# AD_0_V1_01.net
KiCad netlist of a schematic drawn in Altium Designer
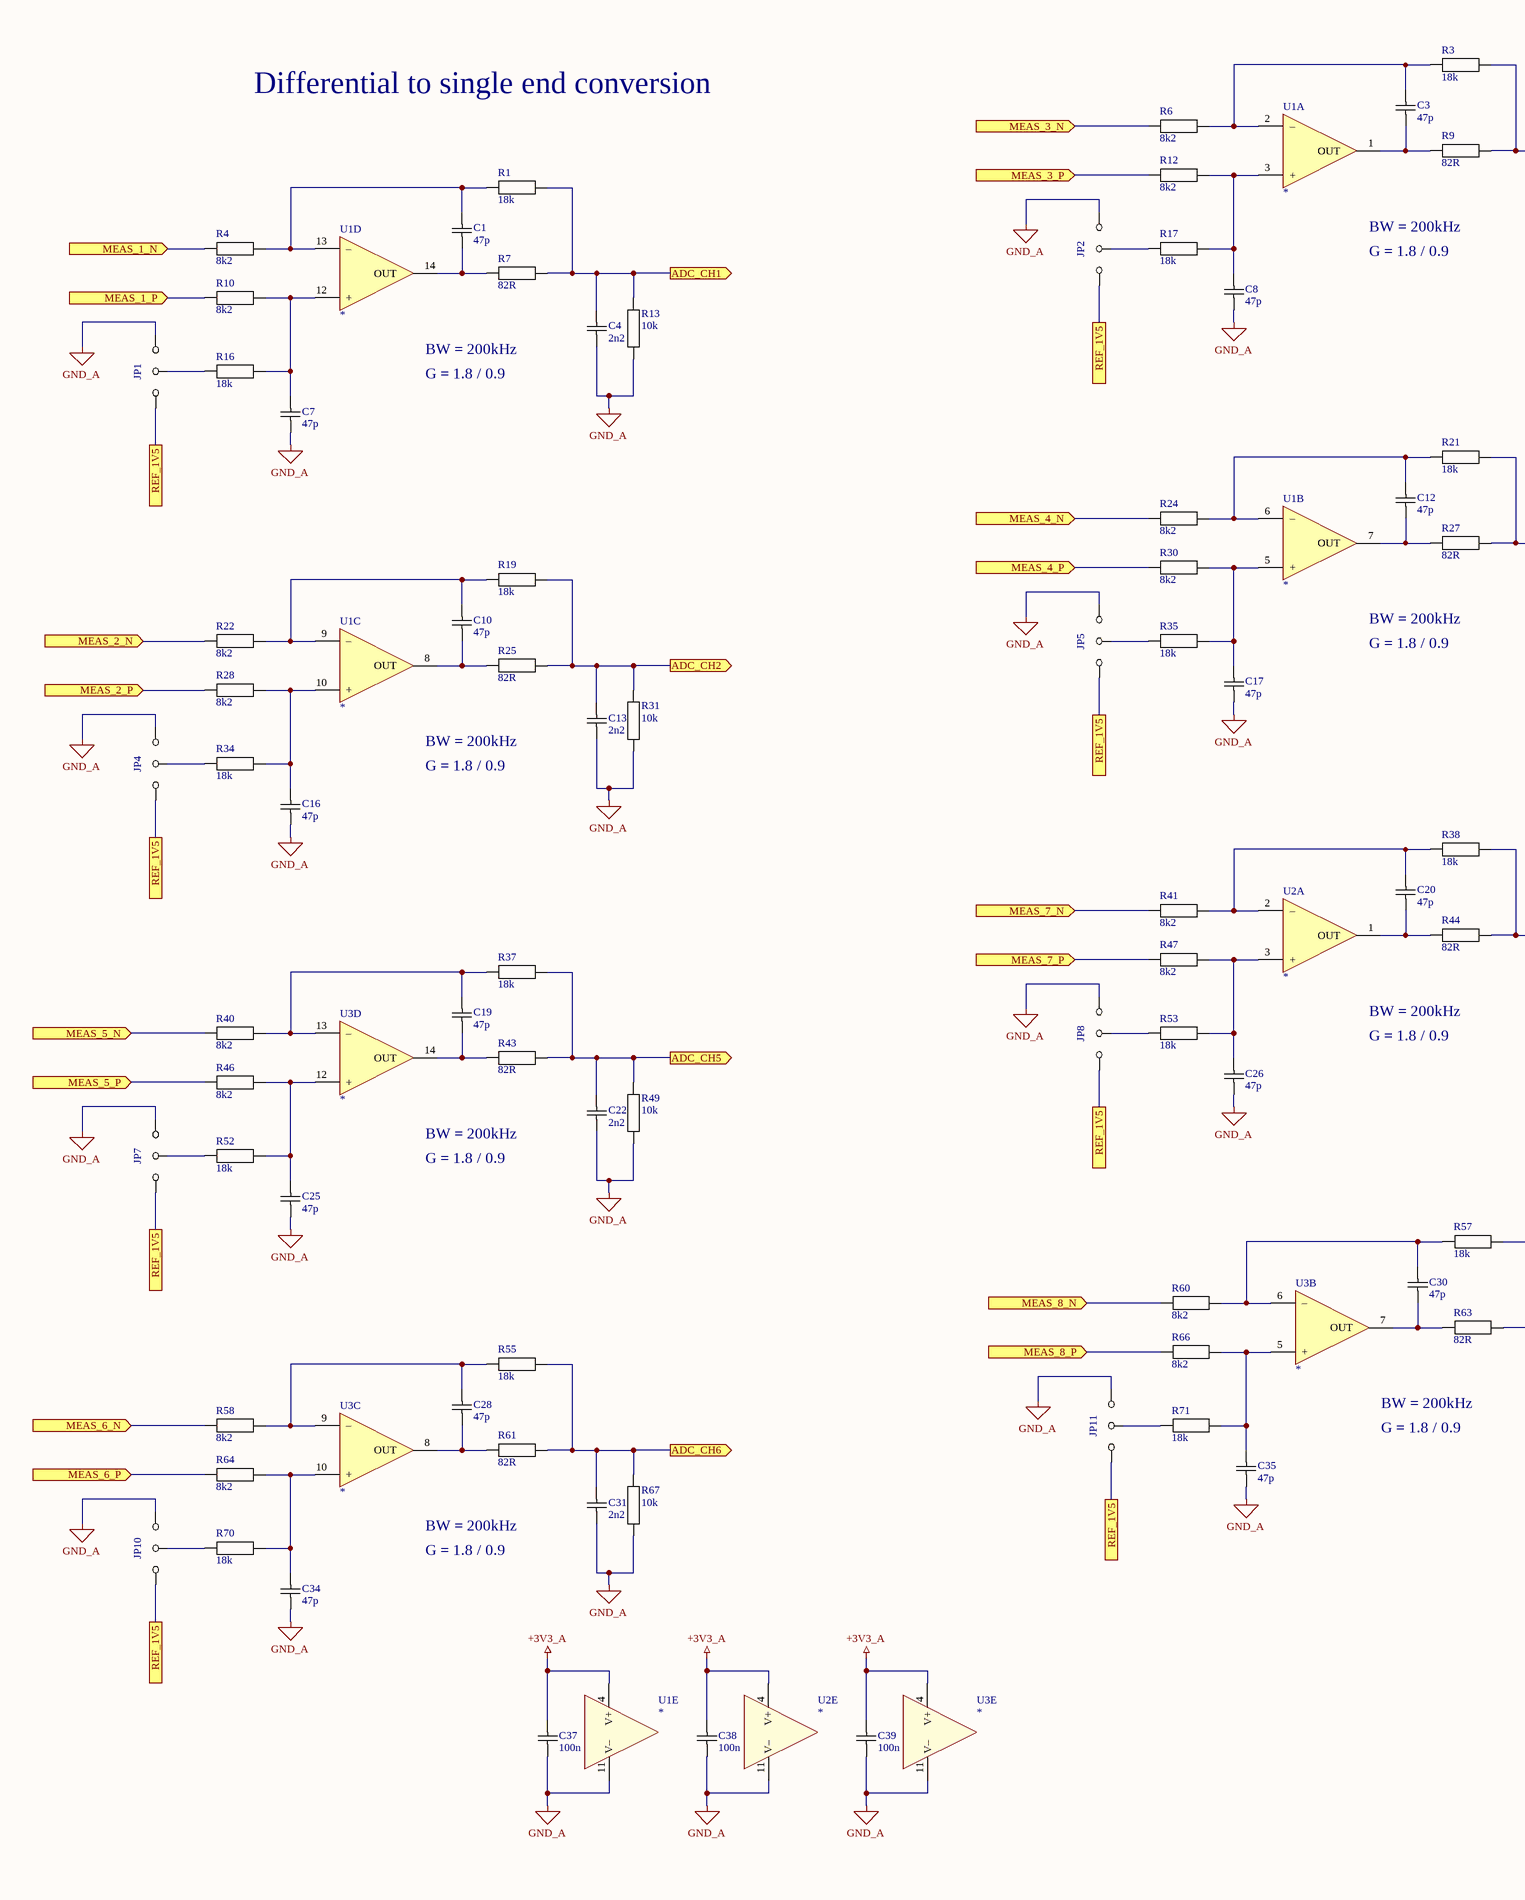
[diagram p0: AD_0_V1_01.SchDoc, left]
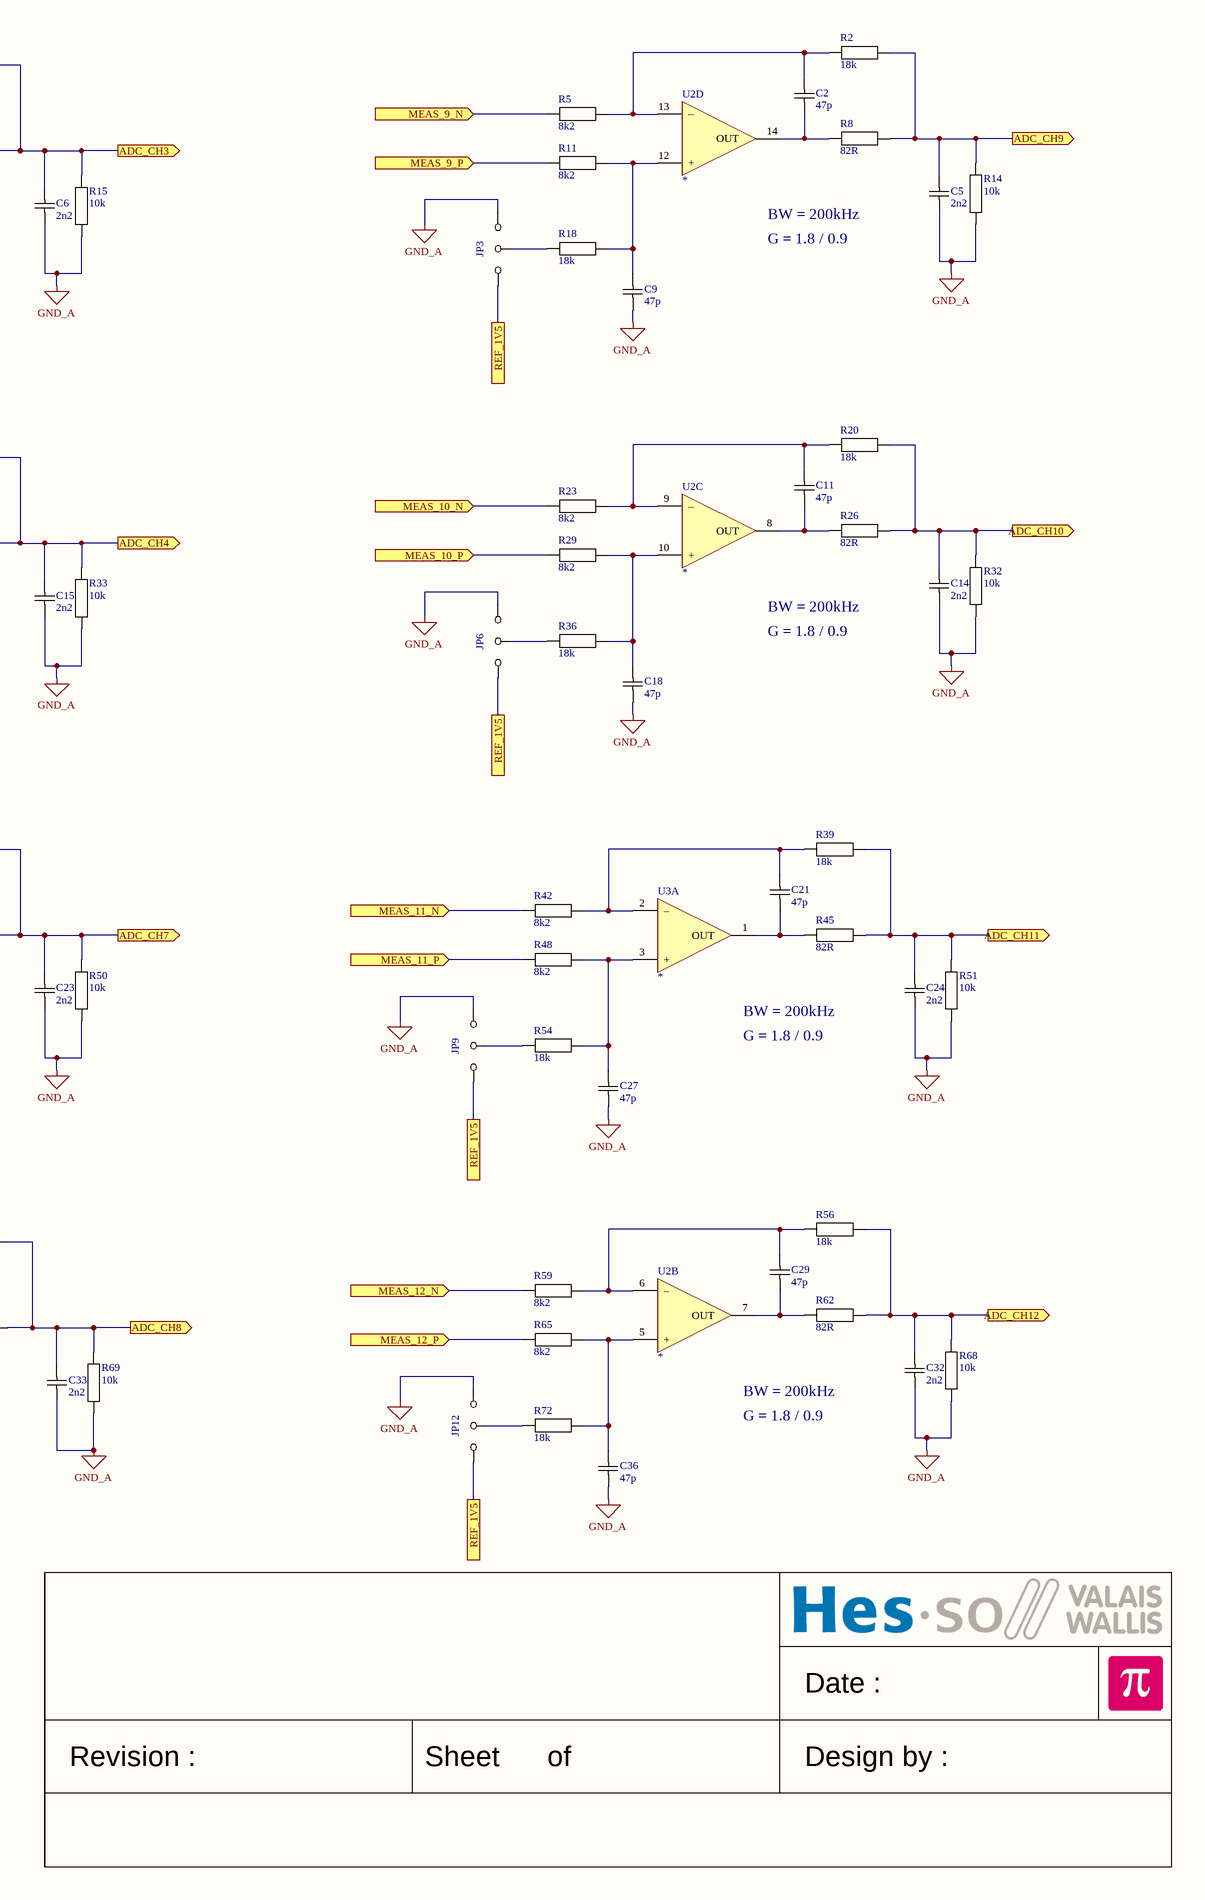
[diagram p1: AD_0_V1_01.SchDoc, right]

(export (version "E")
  (design (tool "Eeschema 10.0.6"))
  (components
    (comp (ref "C1")
      (value "47p")
      (footprint "CAPACITOR 1608 REFLOW")
      (description "Capacitor X7R 10% 50V 1608(0603)")
      (libsource (lib "Capacitor") (part "Capacitor"))
    )
    (comp (ref "C2")
      (value "47p")
      (footprint "CAPACITOR 1608 REFLOW")
      (description "Capacitor X7R 10% 50V 1608(0603)")
      (libsource (lib "Capacitor") (part "Capacitor"))
    )
    (comp (ref "C3")
      (value "47p")
      (footprint "CAPACITOR 1608 REFLOW")
      (description "Capacitor X7R 10% 50V 1608(0603)")
      (libsource (lib "Capacitor") (part "Capacitor"))
    )
    (comp (ref "C4")
      (value "2n2")
      (footprint "CAPACITOR 1608 REFLOW")
      (description "Capacitor X7R 10% 50V 1608(0603)")
      (libsource (lib "Capacitor") (part "Capacitor"))
    )
    (comp (ref "C5")
      (value "2n2")
      (footprint "CAPACITOR 1608 REFLOW")
      (description "Capacitor X7R 10% 50V 1608(0603)")
      (libsource (lib "Capacitor") (part "Capacitor"))
    )
    (comp (ref "C6")
      (value "2n2")
      (footprint "CAPACITOR 1608 REFLOW")
      (description "Capacitor X7R 10% 50V 1608(0603)")
      (libsource (lib "Capacitor") (part "Capacitor"))
    )
    (comp (ref "C7")
      (value "47p")
      (footprint "CAPACITOR 1608 REFLOW")
      (description "Capacitor X7R 10% 50V 1608(0603)")
      (libsource (lib "Capacitor") (part "Capacitor"))
    )
    (comp (ref "C8")
      (value "47p")
      (footprint "CAPACITOR 1608 REFLOW")
      (description "Capacitor X7R 10% 50V 1608(0603)")
      (libsource (lib "Capacitor") (part "Capacitor"))
    )
    (comp (ref "C9")
      (value "47p")
      (footprint "CAPACITOR 1608 REFLOW")
      (description "Capacitor X7R 10% 50V 1608(0603)")
      (libsource (lib "Capacitor") (part "Capacitor"))
    )
    (comp (ref "C10")
      (value "47p")
      (footprint "CAPACITOR 1608 REFLOW")
      (description "Capacitor X7R 10% 50V 1608(0603)")
      (libsource (lib "Capacitor") (part "Capacitor"))
    )
    (comp (ref "C11")
      (value "47p")
      (footprint "CAPACITOR 1608 REFLOW")
      (description "Capacitor X7R 10% 50V 1608(0603)")
      (libsource (lib "Capacitor") (part "Capacitor"))
    )
    (comp (ref "C12")
      (value "47p")
      (footprint "CAPACITOR 1608 REFLOW")
      (description "Capacitor X7R 10% 50V 1608(0603)")
      (libsource (lib "Capacitor") (part "Capacitor"))
    )
    (comp (ref "C13")
      (value "2n2")
      (footprint "CAPACITOR 1608 REFLOW")
      (description "Capacitor X7R 10% 50V 1608(0603)")
      (libsource (lib "Capacitor") (part "Capacitor"))
    )
    (comp (ref "C14")
      (value "2n2")
      (footprint "CAPACITOR 1608 REFLOW")
      (description "Capacitor X7R 10% 50V 1608(0603)")
      (libsource (lib "Capacitor") (part "Capacitor"))
    )
    (comp (ref "C15")
      (value "2n2")
      (footprint "CAPACITOR 1608 REFLOW")
      (description "Capacitor X7R 10% 50V 1608(0603)")
      (libsource (lib "Capacitor") (part "Capacitor"))
    )
    (comp (ref "C16")
      (value "47p")
      (footprint "CAPACITOR 1608 REFLOW")
      (description "Capacitor X7R 10% 50V 1608(0603)")
      (libsource (lib "Capacitor") (part "Capacitor"))
    )
    (comp (ref "C17")
      (value "47p")
      (footprint "CAPACITOR 1608 REFLOW")
      (description "Capacitor X7R 10% 50V 1608(0603)")
      (libsource (lib "Capacitor") (part "Capacitor"))
    )
    (comp (ref "C18")
      (value "47p")
      (footprint "CAPACITOR 1608 REFLOW")
      (description "Capacitor X7R 10% 50V 1608(0603)")
      (libsource (lib "Capacitor") (part "Capacitor"))
    )
    (comp (ref "C19")
      (value "47p")
      (footprint "CAPACITOR 1608 REFLOW")
      (description "Capacitor X7R 10% 50V 1608(0603)")
      (libsource (lib "Capacitor") (part "Capacitor"))
    )
    (comp (ref "C20")
      (value "47p")
      (footprint "CAPACITOR 1608 REFLOW")
      (description "Capacitor X7R 10% 50V 1608(0603)")
      (libsource (lib "Capacitor") (part "Capacitor"))
    )
    (comp (ref "C21")
      (value "47p")
      (footprint "CAPACITOR 1608 REFLOW")
      (description "Capacitor X7R 10% 50V 1608(0603)")
      (libsource (lib "Capacitor") (part "Capacitor"))
    )
    (comp (ref "C22")
      (value "2n2")
      (footprint "CAPACITOR 1608 REFLOW")
      (description "Capacitor X7R 10% 50V 1608(0603)")
      (libsource (lib "Capacitor") (part "Capacitor"))
    )
    (comp (ref "C23")
      (value "2n2")
      (footprint "CAPACITOR 1608 REFLOW")
      (description "Capacitor X7R 10% 50V 1608(0603)")
      (libsource (lib "Capacitor") (part "Capacitor"))
    )
    (comp (ref "C24")
      (value "2n2")
      (footprint "CAPACITOR 1608 REFLOW")
      (description "Capacitor X7R 10% 50V 1608(0603)")
      (libsource (lib "Capacitor") (part "Capacitor"))
    )
    (comp (ref "C25")
      (value "47p")
      (footprint "CAPACITOR 1608 REFLOW")
      (description "Capacitor X7R 10% 50V 1608(0603)")
      (libsource (lib "Capacitor") (part "Capacitor"))
    )
    (comp (ref "C26")
      (value "47p")
      (footprint "CAPACITOR 1608 REFLOW")
      (description "Capacitor X7R 10% 50V 1608(0603)")
      (libsource (lib "Capacitor") (part "Capacitor"))
    )
    (comp (ref "C27")
      (value "47p")
      (footprint "CAPACITOR 1608 REFLOW")
      (description "Capacitor X7R 10% 50V 1608(0603)")
      (libsource (lib "Capacitor") (part "Capacitor"))
    )
    (comp (ref "C28")
      (value "47p")
      (footprint "CAPACITOR 1608 REFLOW")
      (description "Capacitor X7R 10% 50V 1608(0603)")
      (libsource (lib "Capacitor") (part "Capacitor"))
    )
    (comp (ref "C29")
      (value "47p")
      (footprint "CAPACITOR 1608 REFLOW")
      (description "Capacitor X7R 10% 50V 1608(0603)")
      (libsource (lib "Capacitor") (part "Capacitor"))
    )
    (comp (ref "C30")
      (value "47p")
      (footprint "CAPACITOR 1608 REFLOW")
      (description "Capacitor X7R 10% 50V 1608(0603)")
      (libsource (lib "Capacitor") (part "Capacitor"))
    )
    (comp (ref "C31")
      (value "2n2")
      (footprint "CAPACITOR 1608 REFLOW")
      (description "Capacitor X7R 10% 50V 1608(0603)")
      (libsource (lib "Capacitor") (part "Capacitor"))
    )
    (comp (ref "C32")
      (value "2n2")
      (footprint "CAPACITOR 1608 REFLOW")
      (description "Capacitor X7R 10% 50V 1608(0603)")
      (libsource (lib "Capacitor") (part "Capacitor"))
    )
    (comp (ref "C33")
      (value "2n2")
      (footprint "CAPACITOR 1608 REFLOW")
      (description "Capacitor X7R 10% 50V 1608(0603)")
      (libsource (lib "Capacitor") (part "Capacitor"))
    )
    (comp (ref "C34")
      (value "47p")
      (footprint "CAPACITOR 1608 REFLOW")
      (description "Capacitor X7R 10% 50V 1608(0603)")
      (libsource (lib "Capacitor") (part "Capacitor"))
    )
    (comp (ref "C35")
      (value "47p")
      (footprint "CAPACITOR 1608 REFLOW")
      (description "Capacitor X7R 10% 50V 1608(0603)")
      (libsource (lib "Capacitor") (part "Capacitor"))
    )
    (comp (ref "C36")
      (value "47p")
      (footprint "CAPACITOR 1608 REFLOW")
      (description "Capacitor X7R 10% 50V 1608(0603)")
      (libsource (lib "Capacitor") (part "Capacitor"))
    )
    (comp (ref "C37")
      (value "100n")
      (footprint "CAPACITOR 1608 REFLOW")
      (description "Capacitor X7R 10% 50V 1608(0603)")
      (libsource (lib "Capacitor") (part "Capacitor"))
    )
    (comp (ref "C38")
      (value "100n")
      (footprint "CAPACITOR 1608 REFLOW")
      (description "Capacitor X7R 10% 50V 1608(0603)")
      (libsource (lib "Capacitor") (part "Capacitor"))
    )
    (comp (ref "C39")
      (value "100n")
      (footprint "CAPACITOR 1608 REFLOW")
      (description "Capacitor X7R 10% 50V 1608(0603)")
      (libsource (lib "Capacitor") (part "Capacitor"))
    )
    (comp (ref "JP1")
      (value "{Value}")
      (footprint "JUMPER3 SMD 1608")
      (description "JUMPER 3 POS")
      (libsource (lib "Jumper") (part "JUMPER 3 POS"))
    )
    (comp (ref "JP2")
      (value "{Value}")
      (footprint "JUMPER3 SMD 1608")
      (description "JUMPER 3 POS")
      (libsource (lib "Jumper") (part "JUMPER 3 POS"))
    )
    (comp (ref "JP3")
      (value "{Value}")
      (footprint "JUMPER3 SMD 1608")
      (description "JUMPER 3 POS")
      (libsource (lib "Jumper") (part "JUMPER 3 POS"))
    )
    (comp (ref "JP4")
      (value "{Value}")
      (footprint "JUMPER3 SMD 1608")
      (description "JUMPER 3 POS")
      (libsource (lib "Jumper") (part "JUMPER 3 POS"))
    )
    (comp (ref "JP5")
      (value "{Value}")
      (footprint "JUMPER3 SMD 1608")
      (description "JUMPER 3 POS")
      (libsource (lib "Jumper") (part "JUMPER 3 POS"))
    )
    (comp (ref "JP6")
      (value "{Value}")
      (footprint "JUMPER3 SMD 1608")
      (description "JUMPER 3 POS")
      (libsource (lib "Jumper") (part "JUMPER 3 POS"))
    )
    (comp (ref "JP7")
      (value "{Value}")
      (footprint "JUMPER3 SMD 1608")
      (description "JUMPER 3 POS")
      (libsource (lib "Jumper") (part "JUMPER 3 POS"))
    )
    (comp (ref "JP8")
      (value "{Value}")
      (footprint "JUMPER3 SMD 1608")
      (description "JUMPER 3 POS")
      (libsource (lib "Jumper") (part "JUMPER 3 POS"))
    )
    (comp (ref "JP9")
      (value "{Value}")
      (footprint "JUMPER3 SMD 1608")
      (description "JUMPER 3 POS")
      (libsource (lib "Jumper") (part "JUMPER 3 POS"))
    )
    (comp (ref "JP10")
      (value "{Value}")
      (footprint "JUMPER3 SMD 1608")
      (description "JUMPER 3 POS")
      (libsource (lib "Jumper") (part "JUMPER 3 POS"))
    )
    (comp (ref "JP11")
      (value "{Value}")
      (footprint "JUMPER3 SMD 1608")
      (description "JUMPER 3 POS")
      (libsource (lib "Jumper") (part "JUMPER 3 POS"))
    )
    (comp (ref "JP12")
      (value "{Value}")
      (footprint "JUMPER3 SMD 1608")
      (description "JUMPER 3 POS")
      (libsource (lib "Jumper") (part "JUMPER 3 POS"))
    )
    (comp (ref "R1")
      (value "18k")
      (footprint "RESISTOR 1608 REFLOW")
      (description "Resistor 1% 50V 100mW 1608(0603)")
      (libsource (lib "Resistor") (part "Resistor"))
    )
    (comp (ref "R2")
      (value "18k")
      (footprint "RESISTOR 1608 REFLOW")
      (description "Resistor 1% 50V 100mW 1608(0603)")
      (libsource (lib "Resistor") (part "Resistor"))
    )
    (comp (ref "R3")
      (value "18k")
      (footprint "RESISTOR 1608 REFLOW")
      (description "Resistor 1% 50V 100mW 1608(0603)")
      (libsource (lib "Resistor") (part "Resistor"))
    )
    (comp (ref "R4")
      (value "8k2")
      (footprint "RESISTOR 1608 REFLOW")
      (description "Resistor 1% 50V 100mW 1608(0603)")
      (libsource (lib "Resistor") (part "Resistor"))
    )
    (comp (ref "R5")
      (value "8k2")
      (footprint "RESISTOR 1608 REFLOW")
      (description "Resistor 1% 50V 100mW 1608(0603)")
      (libsource (lib "Resistor") (part "Resistor"))
    )
    (comp (ref "R6")
      (value "8k2")
      (footprint "RESISTOR 1608 REFLOW")
      (description "Resistor 1% 50V 100mW 1608(0603)")
      (libsource (lib "Resistor") (part "Resistor"))
    )
    (comp (ref "R7")
      (value "82R")
      (footprint "RESISTOR 1608 REFLOW")
      (description "Resistor 1% 50V 100mW 1608(0603)")
      (libsource (lib "Resistor") (part "Resistor"))
    )
    (comp (ref "R8")
      (value "82R")
      (footprint "RESISTOR 1608 REFLOW")
      (description "Resistor 1% 50V 100mW 1608(0603)")
      (libsource (lib "Resistor") (part "Resistor"))
    )
    (comp (ref "R9")
      (value "82R")
      (footprint "RESISTOR 1608 REFLOW")
      (description "Resistor 1% 50V 100mW 1608(0603)")
      (libsource (lib "Resistor") (part "Resistor"))
    )
    (comp (ref "R10")
      (value "8k2")
      (footprint "RESISTOR 1608 REFLOW")
      (description "Resistor 1% 50V 100mW 1608(0603)")
      (libsource (lib "Resistor") (part "Resistor"))
    )
    (comp (ref "R11")
      (value "8k2")
      (footprint "RESISTOR 1608 REFLOW")
      (description "Resistor 1% 50V 100mW 1608(0603)")
      (libsource (lib "Resistor") (part "Resistor"))
    )
    (comp (ref "R12")
      (value "8k2")
      (footprint "RESISTOR 1608 REFLOW")
      (description "Resistor 1% 50V 100mW 1608(0603)")
      (libsource (lib "Resistor") (part "Resistor"))
    )
    (comp (ref "R13")
      (value "10k")
      (footprint "RESISTOR 1608 REFLOW")
      (description "Resistor 1% 50V 100mW 1608(0603)")
      (libsource (lib "Resistor") (part "Resistor"))
    )
    (comp (ref "R14")
      (value "10k")
      (footprint "RESISTOR 1608 REFLOW")
      (description "Resistor 1% 50V 100mW 1608(0603)")
      (libsource (lib "Resistor") (part "Resistor"))
    )
    (comp (ref "R15")
      (value "10k")
      (footprint "RESISTOR 1608 REFLOW")
      (description "Resistor 1% 50V 100mW 1608(0603)")
      (libsource (lib "Resistor") (part "Resistor"))
    )
    (comp (ref "R16")
      (value "18k")
      (footprint "RESISTOR 1608 REFLOW")
      (description "Resistor 1% 50V 100mW 1608(0603)")
      (libsource (lib "Resistor") (part "Resistor"))
    )
    (comp (ref "R17")
      (value "18k")
      (footprint "RESISTOR 1608 REFLOW")
      (description "Resistor 1% 50V 100mW 1608(0603)")
      (libsource (lib "Resistor") (part "Resistor"))
    )
    (comp (ref "R18")
      (value "18k")
      (footprint "RESISTOR 1608 REFLOW")
      (description "Resistor 1% 50V 100mW 1608(0603)")
      (libsource (lib "Resistor") (part "Resistor"))
    )
    (comp (ref "R19")
      (value "18k")
      (footprint "RESISTOR 1608 REFLOW")
      (description "Resistor 1% 50V 100mW 1608(0603)")
      (libsource (lib "Resistor") (part "Resistor"))
    )
    (comp (ref "R20")
      (value "18k")
      (footprint "RESISTOR 1608 REFLOW")
      (description "Resistor 1% 50V 100mW 1608(0603)")
      (libsource (lib "Resistor") (part "Resistor"))
    )
    (comp (ref "R21")
      (value "18k")
      (footprint "RESISTOR 1608 REFLOW")
      (description "Resistor 1% 50V 100mW 1608(0603)")
      (libsource (lib "Resistor") (part "Resistor"))
    )
    (comp (ref "R22")
      (value "8k2")
      (footprint "RESISTOR 1608 REFLOW")
      (description "Resistor 1% 50V 100mW 1608(0603)")
      (libsource (lib "Resistor") (part "Resistor"))
    )
    (comp (ref "R23")
      (value "8k2")
      (footprint "RESISTOR 1608 REFLOW")
      (description "Resistor 1% 50V 100mW 1608(0603)")
      (libsource (lib "Resistor") (part "Resistor"))
    )
    (comp (ref "R24")
      (value "8k2")
      (footprint "RESISTOR 1608 REFLOW")
      (description "Resistor 1% 50V 100mW 1608(0603)")
      (libsource (lib "Resistor") (part "Resistor"))
    )
    (comp (ref "R25")
      (value "82R")
      (footprint "RESISTOR 1608 REFLOW")
      (description "Resistor 1% 50V 100mW 1608(0603)")
      (libsource (lib "Resistor") (part "Resistor"))
    )
    (comp (ref "R26")
      (value "82R")
      (footprint "RESISTOR 1608 REFLOW")
      (description "Resistor 1% 50V 100mW 1608(0603)")
      (libsource (lib "Resistor") (part "Resistor"))
    )
    (comp (ref "R27")
      (value "82R")
      (footprint "RESISTOR 1608 REFLOW")
      (description "Resistor 1% 50V 100mW 1608(0603)")
      (libsource (lib "Resistor") (part "Resistor"))
    )
    (comp (ref "R28")
      (value "8k2")
      (footprint "RESISTOR 1608 REFLOW")
      (description "Resistor 1% 50V 100mW 1608(0603)")
      (libsource (lib "Resistor") (part "Resistor"))
    )
    (comp (ref "R29")
      (value "8k2")
      (footprint "RESISTOR 1608 REFLOW")
      (description "Resistor 1% 50V 100mW 1608(0603)")
      (libsource (lib "Resistor") (part "Resistor"))
    )
    (comp (ref "R30")
      (value "8k2")
      (footprint "RESISTOR 1608 REFLOW")
      (description "Resistor 1% 50V 100mW 1608(0603)")
      (libsource (lib "Resistor") (part "Resistor"))
    )
    (comp (ref "R31")
      (value "10k")
      (footprint "RESISTOR 1608 REFLOW")
      (description "Resistor 1% 50V 100mW 1608(0603)")
      (libsource (lib "Resistor") (part "Resistor"))
    )
    (comp (ref "R32")
      (value "10k")
      (footprint "RESISTOR 1608 REFLOW")
      (description "Resistor 1% 50V 100mW 1608(0603)")
      (libsource (lib "Resistor") (part "Resistor"))
    )
    (comp (ref "R33")
      (value "10k")
      (footprint "RESISTOR 1608 REFLOW")
      (description "Resistor 1% 50V 100mW 1608(0603)")
      (libsource (lib "Resistor") (part "Resistor"))
    )
    (comp (ref "R34")
      (value "18k")
      (footprint "RESISTOR 1608 REFLOW")
      (description "Resistor 1% 50V 100mW 1608(0603)")
      (libsource (lib "Resistor") (part "Resistor"))
    )
    (comp (ref "R35")
      (value "18k")
      (footprint "RESISTOR 1608 REFLOW")
      (description "Resistor 1% 50V 100mW 1608(0603)")
      (libsource (lib "Resistor") (part "Resistor"))
    )
    (comp (ref "R36")
      (value "18k")
      (footprint "RESISTOR 1608 REFLOW")
      (description "Resistor 1% 50V 100mW 1608(0603)")
      (libsource (lib "Resistor") (part "Resistor"))
    )
    (comp (ref "R37")
      (value "18k")
      (footprint "RESISTOR 1608 REFLOW")
      (description "Resistor 1% 50V 100mW 1608(0603)")
      (libsource (lib "Resistor") (part "Resistor"))
    )
    (comp (ref "R38")
      (value "18k")
      (footprint "RESISTOR 1608 REFLOW")
      (description "Resistor 1% 50V 100mW 1608(0603)")
      (libsource (lib "Resistor") (part "Resistor"))
    )
    (comp (ref "R39")
      (value "18k")
      (footprint "RESISTOR 1608 REFLOW")
      (description "Resistor 1% 50V 100mW 1608(0603)")
      (libsource (lib "Resistor") (part "Resistor"))
    )
    (comp (ref "R40")
      (value "8k2")
      (footprint "RESISTOR 1608 REFLOW")
      (description "Resistor 1% 50V 100mW 1608(0603)")
      (libsource (lib "Resistor") (part "Resistor"))
    )
    (comp (ref "R41")
      (value "8k2")
      (footprint "RESISTOR 1608 REFLOW")
      (description "Resistor 1% 50V 100mW 1608(0603)")
      (libsource (lib "Resistor") (part "Resistor"))
    )
    (comp (ref "R42")
      (value "8k2")
      (footprint "RESISTOR 1608 REFLOW")
      (description "Resistor 1% 50V 100mW 1608(0603)")
      (libsource (lib "Resistor") (part "Resistor"))
    )
    (comp (ref "R43")
      (value "82R")
      (footprint "RESISTOR 1608 REFLOW")
      (description "Resistor 1% 50V 100mW 1608(0603)")
      (libsource (lib "Resistor") (part "Resistor"))
    )
    (comp (ref "R44")
      (value "82R")
      (footprint "RESISTOR 1608 REFLOW")
      (description "Resistor 1% 50V 100mW 1608(0603)")
      (libsource (lib "Resistor") (part "Resistor"))
    )
    (comp (ref "R45")
      (value "82R")
      (footprint "RESISTOR 1608 REFLOW")
      (description "Resistor 1% 50V 100mW 1608(0603)")
      (libsource (lib "Resistor") (part "Resistor"))
    )
    (comp (ref "R46")
      (value "8k2")
      (footprint "RESISTOR 1608 REFLOW")
      (description "Resistor 1% 50V 100mW 1608(0603)")
      (libsource (lib "Resistor") (part "Resistor"))
    )
    (comp (ref "R47")
      (value "8k2")
      (footprint "RESISTOR 1608 REFLOW")
      (description "Resistor 1% 50V 100mW 1608(0603)")
      (libsource (lib "Resistor") (part "Resistor"))
    )
    (comp (ref "R48")
      (value "8k2")
      (footprint "RESISTOR 1608 REFLOW")
      (description "Resistor 1% 50V 100mW 1608(0603)")
      (libsource (lib "Resistor") (part "Resistor"))
    )
    (comp (ref "R49")
      (value "10k")
      (footprint "RESISTOR 1608 REFLOW")
      (description "Resistor 1% 50V 100mW 1608(0603)")
      (libsource (lib "Resistor") (part "Resistor"))
    )
    (comp (ref "R50")
      (value "10k")
      (footprint "RESISTOR 1608 REFLOW")
      (description "Resistor 1% 50V 100mW 1608(0603)")
      (libsource (lib "Resistor") (part "Resistor"))
    )
    (comp (ref "R51")
      (value "10k")
      (footprint "RESISTOR 1608 REFLOW")
      (description "Resistor 1% 50V 100mW 1608(0603)")
      (libsource (lib "Resistor") (part "Resistor"))
    )
    (comp (ref "R52")
      (value "18k")
      (footprint "RESISTOR 1608 REFLOW")
      (description "Resistor 1% 50V 100mW 1608(0603)")
      (libsource (lib "Resistor") (part "Resistor"))
    )
    (comp (ref "R53")
      (value "18k")
      (footprint "RESISTOR 1608 REFLOW")
      (description "Resistor 1% 50V 100mW 1608(0603)")
      (libsource (lib "Resistor") (part "Resistor"))
    )
    (comp (ref "R54")
      (value "18k")
      (footprint "RESISTOR 1608 REFLOW")
      (description "Resistor 1% 50V 100mW 1608(0603)")
      (libsource (lib "Resistor") (part "Resistor"))
    )
    (comp (ref "R55")
      (value "18k")
      (footprint "RESISTOR 1608 REFLOW")
      (description "Resistor 1% 50V 100mW 1608(0603)")
      (libsource (lib "Resistor") (part "Resistor"))
    )
    (comp (ref "R56")
      (value "18k")
      (footprint "RESISTOR 1608 REFLOW")
      (description "Resistor 1% 50V 100mW 1608(0603)")
      (libsource (lib "Resistor") (part "Resistor"))
    )
    (comp (ref "R57")
      (value "18k")
      (footprint "RESISTOR 1608 REFLOW")
      (description "Resistor 1% 50V 100mW 1608(0603)")
      (libsource (lib "Resistor") (part "Resistor"))
    )
    (comp (ref "R58")
      (value "8k2")
      (footprint "RESISTOR 1608 REFLOW")
      (description "Resistor 1% 50V 100mW 1608(0603)")
      (libsource (lib "Resistor") (part "Resistor"))
    )
    (comp (ref "R59")
      (value "8k2")
      (footprint "RESISTOR 1608 REFLOW")
      (description "Resistor 1% 50V 100mW 1608(0603)")
      (libsource (lib "Resistor") (part "Resistor"))
    )
    (comp (ref "R60")
      (value "8k2")
      (footprint "RESISTOR 1608 REFLOW")
      (description "Resistor 1% 50V 100mW 1608(0603)")
      (libsource (lib "Resistor") (part "Resistor"))
    )
    (comp (ref "R61")
      (value "82R")
      (footprint "RESISTOR 1608 REFLOW")
      (description "Resistor 1% 50V 100mW 1608(0603)")
      (libsource (lib "Resistor") (part "Resistor"))
    )
    (comp (ref "R62")
      (value "82R")
      (footprint "RESISTOR 1608 REFLOW")
      (description "Resistor 1% 50V 100mW 1608(0603)")
      (libsource (lib "Resistor") (part "Resistor"))
    )
    (comp (ref "R63")
      (value "82R")
      (footprint "RESISTOR 1608 REFLOW")
      (description "Resistor 1% 50V 100mW 1608(0603)")
      (libsource (lib "Resistor") (part "Resistor"))
    )
    (comp (ref "R64")
      (value "8k2")
      (footprint "RESISTOR 1608 REFLOW")
      (description "Resistor 1% 50V 100mW 1608(0603)")
      (libsource (lib "Resistor") (part "Resistor"))
    )
    (comp (ref "R65")
      (value "8k2")
      (footprint "RESISTOR 1608 REFLOW")
      (description "Resistor 1% 50V 100mW 1608(0603)")
      (libsource (lib "Resistor") (part "Resistor"))
    )
    (comp (ref "R66")
      (value "8k2")
      (footprint "RESISTOR 1608 REFLOW")
      (description "Resistor 1% 50V 100mW 1608(0603)")
      (libsource (lib "Resistor") (part "Resistor"))
    )
    (comp (ref "R67")
      (value "10k")
      (footprint "RESISTOR 1608 REFLOW")
      (description "Resistor 1% 50V 100mW 1608(0603)")
      (libsource (lib "Resistor") (part "Resistor"))
    )
    (comp (ref "R68")
      (value "10k")
      (footprint "RESISTOR 1608 REFLOW")
      (description "Resistor 1% 50V 100mW 1608(0603)")
      (libsource (lib "Resistor") (part "Resistor"))
    )
    (comp (ref "R69")
      (value "10k")
      (footprint "RESISTOR 1608 REFLOW")
      (description "Resistor 1% 50V 100mW 1608(0603)")
      (libsource (lib "Resistor") (part "Resistor"))
    )
    (comp (ref "R70")
      (value "18k")
      (footprint "RESISTOR 1608 REFLOW")
      (description "Resistor 1% 50V 100mW 1608(0603)")
      (libsource (lib "Resistor") (part "Resistor"))
    )
    (comp (ref "R71")
      (value "18k")
      (footprint "RESISTOR 1608 REFLOW")
      (description "Resistor 1% 50V 100mW 1608(0603)")
      (libsource (lib "Resistor") (part "Resistor"))
    )
    (comp (ref "R72")
      (value "18k")
      (footprint "RESISTOR 1608 REFLOW")
      (description "Resistor 1% 50V 100mW 1608(0603)")
      (libsource (lib "Resistor") (part "Resistor"))
    )
    (comp (ref "U1")
      (value "*")
      (footprint "SO14 P1.27 C4.0X8.8 H1.75")
      (description "Generic quad OPA 14 pins")
      (libsource (lib "Amplifier") (part "OPA QUAD"))
    )
    (comp (ref "U2")
      (value "*")
      (footprint "SO14 P1.27 C4.0X8.8 H1.75")
      (description "Generic quad OPA 14 pins")
      (libsource (lib "Amplifier") (part "OPA QUAD"))
    )
    (comp (ref "U3")
      (value "*")
      (footprint "SO14 P1.27 C4.0X8.8 H1.75")
      (description "Generic quad OPA 14 pins")
      (libsource (lib "Amplifier") (part "OPA QUAD"))
    )
  )
  (nets
    (net (code "1") (name "+3V3_A") (class "Default")
      (node (ref "C37") (pin "2") (pinfunction "2_2") (pintype "passive"))
      (node (ref "C38") (pin "2") (pinfunction "2_2") (pintype "passive"))
      (node (ref "C39") (pin "2") (pinfunction "2_2") (pintype "passive"))
      (node (ref "U1") (pin "4") (pinfunction "V+_4") (pintype "passive"))
      (node (ref "U2") (pin "4") (pinfunction "V+_4") (pintype "passive"))
      (node (ref "U3") (pin "4") (pinfunction "V+_4") (pintype "passive"))
    )
    (net (code "2") (name "/ADC_CH1") (class "Default")
      (node (ref "C4") (pin "2") (pinfunction "2_2") (pintype "passive"))
      (node (ref "R1") (pin "2") (pinfunction "2_2") (pintype "passive"))
      (node (ref "R13") (pin "1") (pinfunction "1_1") (pintype "passive"))
      (node (ref "R7") (pin "2") (pinfunction "2_2") (pintype "passive"))
    )
    (net (code "3") (name "/ADC_CH2") (class "Default")
      (node (ref "C13") (pin "2") (pinfunction "2_2") (pintype "passive"))
      (node (ref "R19") (pin "2") (pinfunction "2_2") (pintype "passive"))
      (node (ref "R25") (pin "2") (pinfunction "2_2") (pintype "passive"))
      (node (ref "R31") (pin "1") (pinfunction "1_1") (pintype "passive"))
    )
    (net (code "4") (name "/ADC_CH3") (class "Default")
      (node (ref "C6") (pin "2") (pinfunction "2_2") (pintype "passive"))
      (node (ref "R15") (pin "1") (pinfunction "1_1") (pintype "passive"))
      (node (ref "R3") (pin "2") (pinfunction "2_2") (pintype "passive"))
      (node (ref "R9") (pin "2") (pinfunction "2_2") (pintype "passive"))
    )
    (net (code "5") (name "/ADC_CH4") (class "Default")
      (node (ref "C15") (pin "2") (pinfunction "2_2") (pintype "passive"))
      (node (ref "R21") (pin "2") (pinfunction "2_2") (pintype "passive"))
      (node (ref "R27") (pin "2") (pinfunction "2_2") (pintype "passive"))
      (node (ref "R33") (pin "1") (pinfunction "1_1") (pintype "passive"))
    )
    (net (code "6") (name "/ADC_CH5") (class "Default")
      (node (ref "C22") (pin "2") (pinfunction "2_2") (pintype "passive"))
      (node (ref "R37") (pin "2") (pinfunction "2_2") (pintype "passive"))
      (node (ref "R43") (pin "2") (pinfunction "2_2") (pintype "passive"))
      (node (ref "R49") (pin "1") (pinfunction "1_1") (pintype "passive"))
    )
    (net (code "7") (name "/ADC_CH6") (class "Default")
      (node (ref "C31") (pin "2") (pinfunction "2_2") (pintype "passive"))
      (node (ref "R55") (pin "2") (pinfunction "2_2") (pintype "passive"))
      (node (ref "R61") (pin "2") (pinfunction "2_2") (pintype "passive"))
      (node (ref "R67") (pin "1") (pinfunction "1_1") (pintype "passive"))
    )
    (net (code "8") (name "/ADC_CH7") (class "Default")
      (node (ref "C23") (pin "2") (pinfunction "2_2") (pintype "passive"))
      (node (ref "R38") (pin "2") (pinfunction "2_2") (pintype "passive"))
      (node (ref "R44") (pin "2") (pinfunction "2_2") (pintype "passive"))
      (node (ref "R50") (pin "1") (pinfunction "1_1") (pintype "passive"))
    )
    (net (code "9") (name "/ADC_CH8") (class "Default")
      (node (ref "C33") (pin "2") (pinfunction "2_2") (pintype "passive"))
      (node (ref "R57") (pin "2") (pinfunction "2_2") (pintype "passive"))
      (node (ref "R63") (pin "2") (pinfunction "2_2") (pintype "passive"))
      (node (ref "R69") (pin "1") (pinfunction "1_1") (pintype "passive"))
    )
    (net (code "10") (name "/ADC_CH9") (class "Default")
      (node (ref "C5") (pin "2") (pinfunction "2_2") (pintype "passive"))
      (node (ref "R14") (pin "1") (pinfunction "1_1") (pintype "passive"))
      (node (ref "R2") (pin "2") (pinfunction "2_2") (pintype "passive"))
      (node (ref "R8") (pin "2") (pinfunction "2_2") (pintype "passive"))
    )
    (net (code "11") (name "/ADC_CH10") (class "Default")
      (node (ref "C14") (pin "2") (pinfunction "2_2") (pintype "passive"))
      (node (ref "R20") (pin "2") (pinfunction "2_2") (pintype "passive"))
      (node (ref "R26") (pin "2") (pinfunction "2_2") (pintype "passive"))
      (node (ref "R32") (pin "1") (pinfunction "1_1") (pintype "passive"))
    )
    (net (code "12") (name "/ADC_CH11") (class "Default")
      (node (ref "C24") (pin "2") (pinfunction "2_2") (pintype "passive"))
      (node (ref "R39") (pin "2") (pinfunction "2_2") (pintype "passive"))
      (node (ref "R45") (pin "2") (pinfunction "2_2") (pintype "passive"))
      (node (ref "R51") (pin "1") (pinfunction "1_1") (pintype "passive"))
    )
    (net (code "13") (name "/ADC_CH12") (class "Default")
      (node (ref "C32") (pin "2") (pinfunction "2_2") (pintype "passive"))
      (node (ref "R56") (pin "2") (pinfunction "2_2") (pintype "passive"))
      (node (ref "R62") (pin "2") (pinfunction "2_2") (pintype "passive"))
      (node (ref "R68") (pin "1") (pinfunction "1_1") (pintype "passive"))
    )
    (net (code "14") (name "/MEAS_1_N") (class "Default")
      (node (ref "R4") (pin "1") (pinfunction "1_1") (pintype "passive"))
    )
    (net (code "15") (name "/MEAS_1_P") (class "Default")
      (node (ref "R10") (pin "1") (pinfunction "1_1") (pintype "passive"))
    )
    (net (code "16") (name "/MEAS_2_N") (class "Default")
      (node (ref "R22") (pin "1") (pinfunction "1_1") (pintype "passive"))
    )
    (net (code "17") (name "/MEAS_2_P") (class "Default")
      (node (ref "R28") (pin "1") (pinfunction "1_1") (pintype "passive"))
    )
    (net (code "18") (name "/MEAS_3_N") (class "Default")
      (node (ref "R6") (pin "1") (pinfunction "1_1") (pintype "passive"))
    )
    (net (code "19") (name "/MEAS_3_P") (class "Default")
      (node (ref "R12") (pin "1") (pinfunction "1_1") (pintype "passive"))
    )
    (net (code "20") (name "/MEAS_4_N") (class "Default")
      (node (ref "R24") (pin "1") (pinfunction "1_1") (pintype "passive"))
    )
    (net (code "21") (name "/MEAS_4_P") (class "Default")
      (node (ref "R30") (pin "1") (pinfunction "1_1") (pintype "passive"))
    )
    (net (code "22") (name "/MEAS_5_N") (class "Default")
      (node (ref "R40") (pin "1") (pinfunction "1_1") (pintype "passive"))
    )
    (net (code "23") (name "/MEAS_5_P") (class "Default")
      (node (ref "R46") (pin "1") (pinfunction "1_1") (pintype "passive"))
    )
    (net (code "24") (name "/MEAS_6_N") (class "Default")
      (node (ref "R58") (pin "1") (pinfunction "1_1") (pintype "passive"))
    )
    (net (code "25") (name "/MEAS_6_P") (class "Default")
      (node (ref "R64") (pin "1") (pinfunction "1_1") (pintype "passive"))
    )
    (net (code "26") (name "/MEAS_7_N") (class "Default")
      (node (ref "R41") (pin "1") (pinfunction "1_1") (pintype "passive"))
    )
    (net (code "27") (name "/MEAS_7_P") (class "Default")
      (node (ref "R47") (pin "1") (pinfunction "1_1") (pintype "passive"))
    )
    (net (code "28") (name "/MEAS_8_N") (class "Default")
      (node (ref "R60") (pin "1") (pinfunction "1_1") (pintype "passive"))
    )
    (net (code "29") (name "/MEAS_8_P") (class "Default")
      (node (ref "R66") (pin "1") (pinfunction "1_1") (pintype "passive"))
    )
    (net (code "30") (name "/MEAS_9_N") (class "Default")
      (node (ref "R5") (pin "1") (pinfunction "1_1") (pintype "passive"))
    )
    (net (code "31") (name "/MEAS_9_P") (class "Default")
      (node (ref "R11") (pin "1") (pinfunction "1_1") (pintype "passive"))
    )
    (net (code "32") (name "/MEAS_10_N") (class "Default")
      (node (ref "R23") (pin "1") (pinfunction "1_1") (pintype "passive"))
    )
    (net (code "33") (name "/MEAS_10_P") (class "Default")
      (node (ref "R29") (pin "1") (pinfunction "1_1") (pintype "passive"))
    )
    (net (code "34") (name "/MEAS_11_N") (class "Default")
      (node (ref "R42") (pin "1") (pinfunction "1_1") (pintype "passive"))
    )
    (net (code "35") (name "/MEAS_11_P") (class "Default")
      (node (ref "R48") (pin "1") (pinfunction "1_1") (pintype "passive"))
    )
    (net (code "36") (name "/MEAS_12_N") (class "Default")
      (node (ref "R59") (pin "1") (pinfunction "1_1") (pintype "passive"))
    )
    (net (code "37") (name "/MEAS_12_P") (class "Default")
      (node (ref "R65") (pin "1") (pinfunction "1_1") (pintype "passive"))
    )
    (net (code "38") (name "/REF_1V5") (class "Default")
      (node (ref "JP1") (pin "1") (pinfunction "1_1") (pintype "passive"))
      (node (ref "JP10") (pin "1") (pinfunction "1_1") (pintype "passive"))
      (node (ref "JP11") (pin "1") (pinfunction "1_1") (pintype "passive"))
      (node (ref "JP12") (pin "1") (pinfunction "1_1") (pintype "passive"))
      (node (ref "JP2") (pin "1") (pinfunction "1_1") (pintype "passive"))
      (node (ref "JP3") (pin "1") (pinfunction "1_1") (pintype "passive"))
      (node (ref "JP4") (pin "1") (pinfunction "1_1") (pintype "passive"))
      (node (ref "JP5") (pin "1") (pinfunction "1_1") (pintype "passive"))
      (node (ref "JP6") (pin "1") (pinfunction "1_1") (pintype "passive"))
      (node (ref "JP7") (pin "1") (pinfunction "1_1") (pintype "passive"))
      (node (ref "JP8") (pin "1") (pinfunction "1_1") (pintype "passive"))
      (node (ref "JP9") (pin "1") (pinfunction "1_1") (pintype "passive"))
    )
    (net (code "39") (name "GND_A") (class "Default")
      (node (ref "C13") (pin "1") (pinfunction "1_1") (pintype "passive"))
      (node (ref "C14") (pin "1") (pinfunction "1_1") (pintype "passive"))
      (node (ref "C15") (pin "1") (pinfunction "1_1") (pintype "passive"))
      (node (ref "C16") (pin "1") (pinfunction "1_1") (pintype "passive"))
      (node (ref "C17") (pin "1") (pinfunction "1_1") (pintype "passive"))
      (node (ref "C18") (pin "1") (pinfunction "1_1") (pintype "passive"))
      (node (ref "C22") (pin "1") (pinfunction "1_1") (pintype "passive"))
      (node (ref "C23") (pin "1") (pinfunction "1_1") (pintype "passive"))
      (node (ref "C24") (pin "1") (pinfunction "1_1") (pintype "passive"))
      (node (ref "C25") (pin "1") (pinfunction "1_1") (pintype "passive"))
      (node (ref "C26") (pin "1") (pinfunction "1_1") (pintype "passive"))
      (node (ref "C27") (pin "1") (pinfunction "1_1") (pintype "passive"))
      (node (ref "C31") (pin "1") (pinfunction "1_1") (pintype "passive"))
      (node (ref "C32") (pin "1") (pinfunction "1_1") (pintype "passive"))
      (node (ref "C33") (pin "1") (pinfunction "1_1") (pintype "passive"))
      (node (ref "C34") (pin "1") (pinfunction "1_1") (pintype "passive"))
      (node (ref "C35") (pin "1") (pinfunction "1_1") (pintype "passive"))
      (node (ref "C36") (pin "1") (pinfunction "1_1") (pintype "passive"))
      (node (ref "C37") (pin "1") (pinfunction "1_1") (pintype "passive"))
      (node (ref "C38") (pin "1") (pinfunction "1_1") (pintype "passive"))
      (node (ref "C39") (pin "1") (pinfunction "1_1") (pintype "passive"))
      (node (ref "C4") (pin "1") (pinfunction "1_1") (pintype "passive"))
      (node (ref "C5") (pin "1") (pinfunction "1_1") (pintype "passive"))
      (node (ref "C6") (pin "1") (pinfunction "1_1") (pintype "passive"))
      (node (ref "C7") (pin "1") (pinfunction "1_1") (pintype "passive"))
      (node (ref "C8") (pin "1") (pinfunction "1_1") (pintype "passive"))
      (node (ref "C9") (pin "1") (pinfunction "1_1") (pintype "passive"))
      (node (ref "JP1") (pin "3") (pinfunction "3_3") (pintype "passive"))
      (node (ref "JP10") (pin "3") (pinfunction "3_3") (pintype "passive"))
      (node (ref "JP11") (pin "3") (pinfunction "3_3") (pintype "passive"))
      (node (ref "JP12") (pin "3") (pinfunction "3_3") (pintype "passive"))
      (node (ref "JP2") (pin "3") (pinfunction "3_3") (pintype "passive"))
      (node (ref "JP3") (pin "3") (pinfunction "3_3") (pintype "passive"))
      (node (ref "JP4") (pin "3") (pinfunction "3_3") (pintype "passive"))
      (node (ref "JP5") (pin "3") (pinfunction "3_3") (pintype "passive"))
      (node (ref "JP6") (pin "3") (pinfunction "3_3") (pintype "passive"))
      (node (ref "JP7") (pin "3") (pinfunction "3_3") (pintype "passive"))
      (node (ref "JP8") (pin "3") (pinfunction "3_3") (pintype "passive"))
      (node (ref "JP9") (pin "3") (pinfunction "3_3") (pintype "passive"))
      (node (ref "R13") (pin "2") (pinfunction "2_2") (pintype "passive"))
      (node (ref "R14") (pin "2") (pinfunction "2_2") (pintype "passive"))
      (node (ref "R15") (pin "2") (pinfunction "2_2") (pintype "passive"))
      (node (ref "R31") (pin "2") (pinfunction "2_2") (pintype "passive"))
      (node (ref "R32") (pin "2") (pinfunction "2_2") (pintype "passive"))
      (node (ref "R33") (pin "2") (pinfunction "2_2") (pintype "passive"))
      (node (ref "R49") (pin "2") (pinfunction "2_2") (pintype "passive"))
      (node (ref "R50") (pin "2") (pinfunction "2_2") (pintype "passive"))
      (node (ref "R51") (pin "2") (pinfunction "2_2") (pintype "passive"))
      (node (ref "R67") (pin "2") (pinfunction "2_2") (pintype "passive"))
      (node (ref "R68") (pin "2") (pinfunction "2_2") (pintype "passive"))
      (node (ref "R69") (pin "2") (pinfunction "2_2") (pintype "passive"))
      (node (ref "U1") (pin "11") (pinfunction "V–_11") (pintype "passive"))
      (node (ref "U2") (pin "11") (pinfunction "V–_11") (pintype "passive"))
      (node (ref "U3") (pin "11") (pinfunction "V–_11") (pintype "passive"))
    )
    (net (code "40") (name "Net-(JP1-Pad2)") (class "Default")
      (node (ref "JP1") (pin "2") (pinfunction "2_2") (pintype "passive"))
      (node (ref "R16") (pin "2") (pinfunction "2_2") (pintype "passive"))
    )
    (net (code "41") (name "Net-(JP2-Pad2)") (class "Default")
      (node (ref "JP2") (pin "2") (pinfunction "2_2") (pintype "passive"))
      (node (ref "R17") (pin "2") (pinfunction "2_2") (pintype "passive"))
    )
    (net (code "42") (name "Net-(JP3-Pad2)") (class "Default")
      (node (ref "JP3") (pin "2") (pinfunction "2_2") (pintype "passive"))
      (node (ref "R18") (pin "2") (pinfunction "2_2") (pintype "passive"))
    )
    (net (code "43") (name "Net-(JP4-Pad2)") (class "Default")
      (node (ref "JP4") (pin "2") (pinfunction "2_2") (pintype "passive"))
      (node (ref "R34") (pin "2") (pinfunction "2_2") (pintype "passive"))
    )
    (net (code "44") (name "Net-(JP5-Pad2)") (class "Default")
      (node (ref "JP5") (pin "2") (pinfunction "2_2") (pintype "passive"))
      (node (ref "R35") (pin "2") (pinfunction "2_2") (pintype "passive"))
    )
    (net (code "45") (name "Net-(JP6-Pad2)") (class "Default")
      (node (ref "JP6") (pin "2") (pinfunction "2_2") (pintype "passive"))
      (node (ref "R36") (pin "2") (pinfunction "2_2") (pintype "passive"))
    )
    (net (code "46") (name "Net-(JP7-Pad2)") (class "Default")
      (node (ref "JP7") (pin "2") (pinfunction "2_2") (pintype "passive"))
      (node (ref "R52") (pin "2") (pinfunction "2_2") (pintype "passive"))
    )
    (net (code "47") (name "Net-(JP8-Pad2)") (class "Default")
      (node (ref "JP8") (pin "2") (pinfunction "2_2") (pintype "passive"))
      (node (ref "R53") (pin "2") (pinfunction "2_2") (pintype "passive"))
    )
    (net (code "48") (name "Net-(JP9-Pad2)") (class "Default")
      (node (ref "JP9") (pin "2") (pinfunction "2_2") (pintype "passive"))
      (node (ref "R54") (pin "2") (pinfunction "2_2") (pintype "passive"))
    )
    (net (code "49") (name "Net-(JP10-Pad2)") (class "Default")
      (node (ref "JP10") (pin "2") (pinfunction "2_2") (pintype "passive"))
      (node (ref "R70") (pin "2") (pinfunction "2_2") (pintype "passive"))
    )
    (net (code "50") (name "Net-(JP11-Pad2)") (class "Default")
      (node (ref "JP11") (pin "2") (pinfunction "2_2") (pintype "passive"))
      (node (ref "R71") (pin "2") (pinfunction "2_2") (pintype "passive"))
    )
    (net (code "51") (name "Net-(JP12-Pad2)") (class "Default")
      (node (ref "JP12") (pin "2") (pinfunction "2_2") (pintype "passive"))
      (node (ref "R72") (pin "2") (pinfunction "2_2") (pintype "passive"))
    )
    (net (code "52") (name "Net-(U1A-+)") (class "Default")
      (node (ref "C8") (pin "2") (pinfunction "2_2") (pintype "passive"))
      (node (ref "R12") (pin "2") (pinfunction "2_2") (pintype "passive"))
      (node (ref "R17") (pin "1") (pinfunction "1_1") (pintype "passive"))
      (node (ref "U1") (pin "3") (pinfunction "+_3") (pintype "passive"))
    )
    (net (code "53") (name "Net-(U1A-OUT)") (class "Default")
      (node (ref "C3") (pin "1") (pinfunction "1_1") (pintype "passive"))
      (node (ref "R9") (pin "1") (pinfunction "1_1") (pintype "passive"))
      (node (ref "U1") (pin "1") (pinfunction "OUT_1") (pintype "passive"))
    )
    (net (code "54") (name "Net-(U1A-–)") (class "Default")
      (node (ref "C3") (pin "2") (pinfunction "2_2") (pintype "passive"))
      (node (ref "R3") (pin "1") (pinfunction "1_1") (pintype "passive"))
      (node (ref "R6") (pin "2") (pinfunction "2_2") (pintype "passive"))
      (node (ref "U1") (pin "2") (pinfunction "–_2") (pintype "passive"))
    )
    (net (code "55") (name "Net-(U1B-+)") (class "Default")
      (node (ref "C17") (pin "2") (pinfunction "2_2") (pintype "passive"))
      (node (ref "R30") (pin "2") (pinfunction "2_2") (pintype "passive"))
      (node (ref "R35") (pin "1") (pinfunction "1_1") (pintype "passive"))
      (node (ref "U1") (pin "5") (pinfunction "+_5") (pintype "passive"))
    )
    (net (code "56") (name "Net-(U1B-OUT)") (class "Default")
      (node (ref "C12") (pin "1") (pinfunction "1_1") (pintype "passive"))
      (node (ref "R27") (pin "1") (pinfunction "1_1") (pintype "passive"))
      (node (ref "U1") (pin "7") (pinfunction "OUT_7") (pintype "passive"))
    )
    (net (code "57") (name "Net-(U1B-–)") (class "Default")
      (node (ref "C12") (pin "2") (pinfunction "2_2") (pintype "passive"))
      (node (ref "R21") (pin "1") (pinfunction "1_1") (pintype "passive"))
      (node (ref "R24") (pin "2") (pinfunction "2_2") (pintype "passive"))
      (node (ref "U1") (pin "6") (pinfunction "–_6") (pintype "passive"))
    )
    (net (code "58") (name "Net-(U1C-+)") (class "Default")
      (node (ref "C16") (pin "2") (pinfunction "2_2") (pintype "passive"))
      (node (ref "R28") (pin "2") (pinfunction "2_2") (pintype "passive"))
      (node (ref "R34") (pin "1") (pinfunction "1_1") (pintype "passive"))
      (node (ref "U1") (pin "10") (pinfunction "+_10") (pintype "passive"))
    )
    (net (code "59") (name "Net-(U1C-OUT)") (class "Default")
      (node (ref "C10") (pin "1") (pinfunction "1_1") (pintype "passive"))
      (node (ref "R25") (pin "1") (pinfunction "1_1") (pintype "passive"))
      (node (ref "U1") (pin "8") (pinfunction "OUT_8") (pintype "passive"))
    )
    (net (code "60") (name "Net-(U1C-–)") (class "Default")
      (node (ref "C10") (pin "2") (pinfunction "2_2") (pintype "passive"))
      (node (ref "R19") (pin "1") (pinfunction "1_1") (pintype "passive"))
      (node (ref "R22") (pin "2") (pinfunction "2_2") (pintype "passive"))
      (node (ref "U1") (pin "9") (pinfunction "–_9") (pintype "passive"))
    )
    (net (code "61") (name "Net-(U1D-+)") (class "Default")
      (node (ref "C7") (pin "2") (pinfunction "2_2") (pintype "passive"))
      (node (ref "R10") (pin "2") (pinfunction "2_2") (pintype "passive"))
      (node (ref "R16") (pin "1") (pinfunction "1_1") (pintype "passive"))
      (node (ref "U1") (pin "12") (pinfunction "+_12") (pintype "passive"))
    )
    (net (code "62") (name "Net-(U1D-OUT)") (class "Default")
      (node (ref "C1") (pin "1") (pinfunction "1_1") (pintype "passive"))
      (node (ref "R7") (pin "1") (pinfunction "1_1") (pintype "passive"))
      (node (ref "U1") (pin "14") (pinfunction "OUT_14") (pintype "passive"))
    )
    (net (code "63") (name "Net-(U1D-–)") (class "Default")
      (node (ref "C1") (pin "2") (pinfunction "2_2") (pintype "passive"))
      (node (ref "R1") (pin "1") (pinfunction "1_1") (pintype "passive"))
      (node (ref "R4") (pin "2") (pinfunction "2_2") (pintype "passive"))
      (node (ref "U1") (pin "13") (pinfunction "–_13") (pintype "passive"))
    )
    (net (code "64") (name "Net-(U2A-+)") (class "Default")
      (node (ref "C26") (pin "2") (pinfunction "2_2") (pintype "passive"))
      (node (ref "R47") (pin "2") (pinfunction "2_2") (pintype "passive"))
      (node (ref "R53") (pin "1") (pinfunction "1_1") (pintype "passive"))
      (node (ref "U2") (pin "3") (pinfunction "+_3") (pintype "passive"))
    )
    (net (code "65") (name "Net-(U2A-OUT)") (class "Default")
      (node (ref "C20") (pin "1") (pinfunction "1_1") (pintype "passive"))
      (node (ref "R44") (pin "1") (pinfunction "1_1") (pintype "passive"))
      (node (ref "U2") (pin "1") (pinfunction "OUT_1") (pintype "passive"))
    )
    (net (code "66") (name "Net-(U2A-–)") (class "Default")
      (node (ref "C20") (pin "2") (pinfunction "2_2") (pintype "passive"))
      (node (ref "R38") (pin "1") (pinfunction "1_1") (pintype "passive"))
      (node (ref "R41") (pin "2") (pinfunction "2_2") (pintype "passive"))
      (node (ref "U2") (pin "2") (pinfunction "–_2") (pintype "passive"))
    )
    (net (code "67") (name "Net-(U2B-+)") (class "Default")
      (node (ref "C36") (pin "2") (pinfunction "2_2") (pintype "passive"))
      (node (ref "R65") (pin "2") (pinfunction "2_2") (pintype "passive"))
      (node (ref "R72") (pin "1") (pinfunction "1_1") (pintype "passive"))
      (node (ref "U2") (pin "5") (pinfunction "+_5") (pintype "passive"))
    )
    (net (code "68") (name "Net-(U2B-OUT)") (class "Default")
      (node (ref "C29") (pin "1") (pinfunction "1_1") (pintype "passive"))
      (node (ref "R62") (pin "1") (pinfunction "1_1") (pintype "passive"))
      (node (ref "U2") (pin "7") (pinfunction "OUT_7") (pintype "passive"))
    )
    (net (code "69") (name "Net-(U2B-–)") (class "Default")
      (node (ref "C29") (pin "2") (pinfunction "2_2") (pintype "passive"))
      (node (ref "R56") (pin "1") (pinfunction "1_1") (pintype "passive"))
      (node (ref "R59") (pin "2") (pinfunction "2_2") (pintype "passive"))
      (node (ref "U2") (pin "6") (pinfunction "–_6") (pintype "passive"))
    )
    (net (code "70") (name "Net-(U2C-+)") (class "Default")
      (node (ref "C18") (pin "2") (pinfunction "2_2") (pintype "passive"))
      (node (ref "R29") (pin "2") (pinfunction "2_2") (pintype "passive"))
      (node (ref "R36") (pin "1") (pinfunction "1_1") (pintype "passive"))
      (node (ref "U2") (pin "10") (pinfunction "+_10") (pintype "passive"))
    )
    (net (code "71") (name "Net-(U2C-OUT)") (class "Default")
      (node (ref "C11") (pin "1") (pinfunction "1_1") (pintype "passive"))
      (node (ref "R26") (pin "1") (pinfunction "1_1") (pintype "passive"))
      (node (ref "U2") (pin "8") (pinfunction "OUT_8") (pintype "passive"))
    )
    (net (code "72") (name "Net-(U2C-–)") (class "Default")
      (node (ref "C11") (pin "2") (pinfunction "2_2") (pintype "passive"))
      (node (ref "R20") (pin "1") (pinfunction "1_1") (pintype "passive"))
      (node (ref "R23") (pin "2") (pinfunction "2_2") (pintype "passive"))
      (node (ref "U2") (pin "9") (pinfunction "–_9") (pintype "passive"))
    )
    (net (code "73") (name "Net-(U2D-+)") (class "Default")
      (node (ref "C9") (pin "2") (pinfunction "2_2") (pintype "passive"))
      (node (ref "R11") (pin "2") (pinfunction "2_2") (pintype "passive"))
      (node (ref "R18") (pin "1") (pinfunction "1_1") (pintype "passive"))
      (node (ref "U2") (pin "12") (pinfunction "+_12") (pintype "passive"))
    )
    (net (code "74") (name "Net-(U2D-OUT)") (class "Default")
      (node (ref "C2") (pin "1") (pinfunction "1_1") (pintype "passive"))
      (node (ref "R8") (pin "1") (pinfunction "1_1") (pintype "passive"))
      (node (ref "U2") (pin "14") (pinfunction "OUT_14") (pintype "passive"))
    )
    (net (code "75") (name "Net-(U2D-–)") (class "Default")
      (node (ref "C2") (pin "2") (pinfunction "2_2") (pintype "passive"))
      (node (ref "R2") (pin "1") (pinfunction "1_1") (pintype "passive"))
      (node (ref "R5") (pin "2") (pinfunction "2_2") (pintype "passive"))
      (node (ref "U2") (pin "13") (pinfunction "–_13") (pintype "passive"))
    )
    (net (code "76") (name "Net-(U3A-+)") (class "Default")
      (node (ref "C27") (pin "2") (pinfunction "2_2") (pintype "passive"))
      (node (ref "R48") (pin "2") (pinfunction "2_2") (pintype "passive"))
      (node (ref "R54") (pin "1") (pinfunction "1_1") (pintype "passive"))
      (node (ref "U3") (pin "3") (pinfunction "+_3") (pintype "passive"))
    )
    (net (code "77") (name "Net-(U3A-OUT)") (class "Default")
      (node (ref "C21") (pin "1") (pinfunction "1_1") (pintype "passive"))
      (node (ref "R45") (pin "1") (pinfunction "1_1") (pintype "passive"))
      (node (ref "U3") (pin "1") (pinfunction "OUT_1") (pintype "passive"))
    )
    (net (code "78") (name "Net-(U3A-–)") (class "Default")
      (node (ref "C21") (pin "2") (pinfunction "2_2") (pintype "passive"))
      (node (ref "R39") (pin "1") (pinfunction "1_1") (pintype "passive"))
      (node (ref "R42") (pin "2") (pinfunction "2_2") (pintype "passive"))
      (node (ref "U3") (pin "2") (pinfunction "–_2") (pintype "passive"))
    )
    (net (code "79") (name "Net-(U3B-+)") (class "Default")
      (node (ref "C35") (pin "2") (pinfunction "2_2") (pintype "passive"))
      (node (ref "R66") (pin "2") (pinfunction "2_2") (pintype "passive"))
      (node (ref "R71") (pin "1") (pinfunction "1_1") (pintype "passive"))
      (node (ref "U3") (pin "5") (pinfunction "+_5") (pintype "passive"))
    )
    (net (code "80") (name "Net-(U3B-OUT)") (class "Default")
      (node (ref "C30") (pin "1") (pinfunction "1_1") (pintype "passive"))
      (node (ref "R63") (pin "1") (pinfunction "1_1") (pintype "passive"))
      (node (ref "U3") (pin "7") (pinfunction "OUT_7") (pintype "passive"))
    )
    (net (code "81") (name "Net-(U3B-–)") (class "Default")
      (node (ref "C30") (pin "2") (pinfunction "2_2") (pintype "passive"))
      (node (ref "R57") (pin "1") (pinfunction "1_1") (pintype "passive"))
      (node (ref "R60") (pin "2") (pinfunction "2_2") (pintype "passive"))
      (node (ref "U3") (pin "6") (pinfunction "–_6") (pintype "passive"))
    )
    (net (code "82") (name "Net-(U3C-+)") (class "Default")
      (node (ref "C34") (pin "2") (pinfunction "2_2") (pintype "passive"))
      (node (ref "R64") (pin "2") (pinfunction "2_2") (pintype "passive"))
      (node (ref "R70") (pin "1") (pinfunction "1_1") (pintype "passive"))
      (node (ref "U3") (pin "10") (pinfunction "+_10") (pintype "passive"))
    )
    (net (code "83") (name "Net-(U3C-OUT)") (class "Default")
      (node (ref "C28") (pin "1") (pinfunction "1_1") (pintype "passive"))
      (node (ref "R61") (pin "1") (pinfunction "1_1") (pintype "passive"))
      (node (ref "U3") (pin "8") (pinfunction "OUT_8") (pintype "passive"))
    )
    (net (code "84") (name "Net-(U3C-–)") (class "Default")
      (node (ref "C28") (pin "2") (pinfunction "2_2") (pintype "passive"))
      (node (ref "R55") (pin "1") (pinfunction "1_1") (pintype "passive"))
      (node (ref "R58") (pin "2") (pinfunction "2_2") (pintype "passive"))
      (node (ref "U3") (pin "9") (pinfunction "–_9") (pintype "passive"))
    )
    (net (code "85") (name "Net-(U3D-+)") (class "Default")
      (node (ref "C25") (pin "2") (pinfunction "2_2") (pintype "passive"))
      (node (ref "R46") (pin "2") (pinfunction "2_2") (pintype "passive"))
      (node (ref "R52") (pin "1") (pinfunction "1_1") (pintype "passive"))
      (node (ref "U3") (pin "12") (pinfunction "+_12") (pintype "passive"))
    )
    (net (code "86") (name "Net-(U3D-OUT)") (class "Default")
      (node (ref "C19") (pin "1") (pinfunction "1_1") (pintype "passive"))
      (node (ref "R43") (pin "1") (pinfunction "1_1") (pintype "passive"))
      (node (ref "U3") (pin "14") (pinfunction "OUT_14") (pintype "passive"))
    )
    (net (code "87") (name "Net-(U3D-–)") (class "Default")
      (node (ref "C19") (pin "2") (pinfunction "2_2") (pintype "passive"))
      (node (ref "R37") (pin "1") (pinfunction "1_1") (pintype "passive"))
      (node (ref "R40") (pin "2") (pinfunction "2_2") (pintype "passive"))
      (node (ref "U3") (pin "13") (pinfunction "–_13") (pintype "passive"))
    )
  )
)
